# mcu.net
KiCad netlist of a schematic drawn in Altium Designer
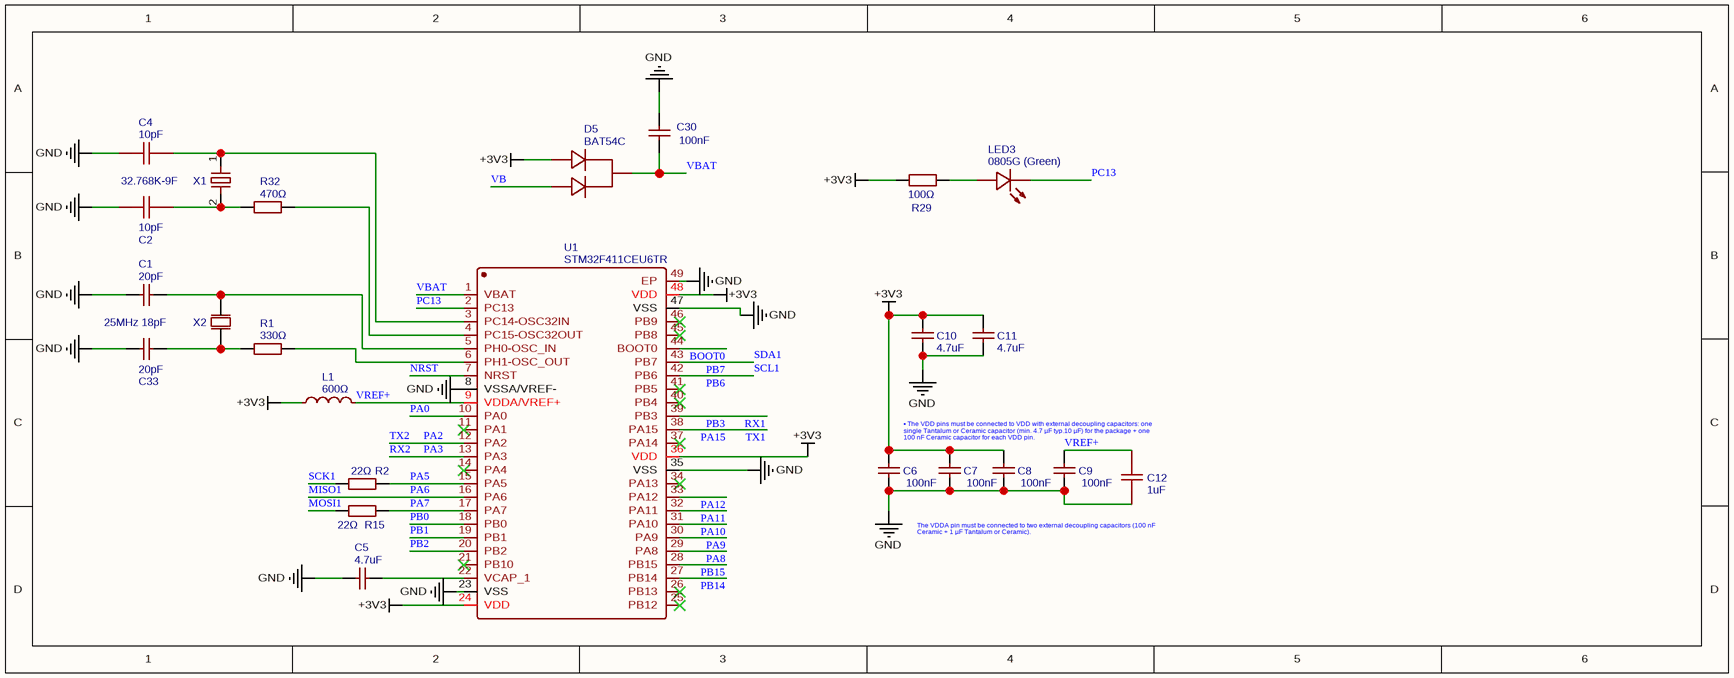
[diagram p0: mcu.schdoc]

(export (version "E")
  (design (tool "Eeschema 10.0.6"))
  (components
    (comp (ref "C1")
      (value "20pF")
      (fields (field (name "MANUFACTURER") "FH(风华)") (field (name "MANUFACTURER PART") "0402CG200J500NT"))
      (libsource (lib "") (part "root_0_20pF__1"))
    )
    (comp (ref "C2")
      (value "10pF")
      (fields
        (field (name "MANUFACTURER") "SAMSUNG(三星)")
        (field (name "MANUFACTURER PART") "CL05C100JB5NNNC")
      )
      (libsource (lib "") (part "root_0_10pF__1"))
    )
    (comp (ref "C4")
      (value "10pF")
      (fields
        (field (name "MANUFACTURER") "SAMSUNG(三星)")
        (field (name "MANUFACTURER PART") "CL05C100JB5NNNC")
      )
      (libsource (lib "altium-import") (part "root_0_10pF_"))
    )
    (comp (ref "C5")
      (value "4.7uF")
      (fields
        (field (name "MANUFACTURER PART") "CL05A475MP5NRNC")
        (field (name "MANUFACTURER") "SAMSUNG(三星)")
      )
      (libsource (lib "altium-import") (part "root_0_4.7uF_"))
    )
    (comp (ref "C6")
      (value "100nF")
      (fields
        (field (name "MANUFACTURER PART") "CL05B104KO5NNNC")
        (field (name "MANUFACTURER") "SAMSUNG(三星)")
      )
      (libsource (lib "altium-import") (part "root_3_100nF_"))
    )
    (comp (ref "C7")
      (value "100nF")
      (fields
        (field (name "MANUFACTURER PART") "CL05B104KO5NNNC")
        (field (name "MANUFACTURER") "SAMSUNG(三星)")
      )
      (libsource (lib "altium-import") (part "root_3_100nF_"))
    )
    (comp (ref "C8")
      (value "100nF")
      (fields
        (field (name "MANUFACTURER PART") "CL05B104KO5NNNC")
        (field (name "MANUFACTURER") "SAMSUNG(三星)")
      )
      (libsource (lib "altium-import") (part "root_3_100nF_"))
    )
    (comp (ref "C9")
      (value "100nF")
      (fields
        (field (name "MANUFACTURER PART") "CL05B104KO5NNNC")
        (field (name "MANUFACTURER") "SAMSUNG(三星)")
      )
      (libsource (lib "altium-import") (part "root_3_100nF_"))
    )
    (comp (ref "C10")
      (value "4.7uF")
      (fields
        (field (name "MANUFACTURER PART") "CL05A475MP5NRNC")
        (field (name "MANUFACTURER") "SAMSUNG(三星)")
      )
      (libsource (lib "altium-import") (part "root_3_4.7uF_"))
    )
    (comp (ref "C11")
      (value "4.7uF")
      (fields
        (field (name "MANUFACTURER PART") "CL05A475MP5NRNC")
        (field (name "MANUFACTURER") "SAMSUNG(三星)")
      )
      (libsource (lib "altium-import") (part "root_3_4.7uF_"))
    )
    (comp (ref "C12")
      (value "1uF")
      (fields
        (field (name "MANUFACTURER") "SAMSUNG(三星)")
        (field (name "MANUFACTURER PART") "CL05A105KA5NQNC")
      )
      (libsource (lib "altium-import") (part "root_3_1uF_"))
    )
    (comp (ref "C30")
      (value "100nF")
      (fields
        (field (name "MANUFACTURER PART") "CL05B104KO5NNNC")
        (field (name "MANUFACTURER") "SAMSUNG(三星)")
      )
      (libsource (lib "altium-import") (part "root_3_100nF_"))
    )
    (comp (ref "C33")
      (value "20pF")
      (fields (field (name "MANUFACTURER") "FH(风华)") (field (name "MANUFACTURER PART") "0402CG200J500NT"))
      (libsource (lib "altium-import") (part "root_0_20pF_"))
    )
    (comp (ref "D5")
      (value "BAT54C")
      (fields (field (name "MANUFACTURER") "CJ(江苏长电/长晶)"))
      (libsource (lib "altium-import") (part "root_0_BAT54C_"))
    )
    (comp (ref "L1")
      (value "600Ω")
      (fields (field (name "MANUFACTURER") "Sunlord(顺络)") (field (name "MANUFACTURER PART") "GZ1608D601TF"))
      (libsource (lib "altium-import") (part "root_0_600Ω_"))
    )
    (comp (ref "LED3")
      (value "0805G (Green)")
      (fields (field (name "MANUFACTURER") "KENTO") (field (name "MANUFACTURER PART") "KT-0805翠绿"))
      (libsource (lib "altium-import") (part "root_2_0805G (Green)_"))
    )
    (comp (ref "R1")
      (value "330Ω")
      (fields
        (field (name "MANUFACTURER") "UNI-ROYAL(厚声)")
        (field (name "MANUFACTURER PART") "0402WGF3300TCE")
      )
      (libsource (lib "altium-import") (part "root_0_330Ω_"))
    )
    (comp (ref "R2")
      (value "22Ω")
      (fields
        (field (name "MANUFACTURER") "UNI-ROYAL(厚声)")
        (field (name "MANUFACTURER PART") "0402WGF220JTCE")
      )
      (libsource (lib "altium-import") (part "root_0_22Ω_"))
    )
    (comp (ref "R15")
      (value "22Ω")
      (fields
        (field (name "MANUFACTURER") "UNI-ROYAL(厚声)")
        (field (name "MANUFACTURER PART") "0402WGF220JTCE")
      )
      (libsource (lib "altium-import") (part "root_0_22Ω_"))
    )
    (comp (ref "R29")
      (value "100Ω")
      (fields
        (field (name "MANUFACTURER") "UNI-ROYAL(厚声)")
        (field (name "MANUFACTURER PART") "0402WGF1000TCE")
      )
      (libsource (lib "altium-import") (part "root_0_100Ω_"))
    )
    (comp (ref "R32")
      (value "470Ω")
      (fields
        (field (name "MANUFACTURER") "UNI-ROYAL(厚声)")
        (field (name "MANUFACTURER PART") "0402WGF4700TCE")
      )
      (libsource (lib "altium-import") (part "root_0_470Ω_"))
    )
    (comp (ref "U1")
      (value "STM32F411CEU6TR")
      (fields (field (name "MANUFACTURER") "ST(意法半导体)") (field (name "CONTRIBUTOR") "LCSC"))
      (libsource (lib "altium-import") (part "root_0_STM32F411CEU6TR_"))
    )
    (comp (ref "X1")
      (value "32.768K-9F")
      (fields
        (field (name "MANUFACTURER PART") "CMTV-T1A-32.768K-12.5PF-20PPM")
        (field (name "CONTRIBUTOR") "lcsc")
      )
      (libsource (lib "altium-import") (part "root_3_32.768K-9F_"))
    )
    (comp (ref "X2")
      (value "25MHz 18pF")
      (fields
        (field (name "MANUFACTURER") "ABRACON")
        (field (name "MANUFACTURER PART") "ABM3-25.000MHZ-D2Y-T")
        (field (name "CONTRIBUTOR") "LCSC")
      )
      (libsource (lib "altium-import") (part "root_3_25MHz 18pF_"))
    )
  )
  (nets
    (net (code "1") (name "+3V3") (class "Default")
      (node (ref "C10") (pin "1") (pinfunction "1_1") (pintype "passive"))
      (node (ref "C11") (pin "1") (pinfunction "1_1") (pintype "passive"))
      (node (ref "C6") (pin "2") (pinfunction "2_2") (pintype "passive"))
      (node (ref "C7") (pin "2") (pinfunction "2_2") (pintype "passive"))
      (node (ref "C8") (pin "2") (pinfunction "2_2") (pintype "passive"))
      (node (ref "D5") (pin "1") (pinfunction "A1_1") (pintype "passive"))
      (node (ref "L1") (pin "1") (pinfunction "1_1") (pintype "passive"))
      (node (ref "R29") (pin "1") (pinfunction "1_1") (pintype "passive"))
      (node (ref "U1") (pin "24") (pinfunction "VDD_24") (pintype "passive"))
      (node (ref "U1") (pin "36") (pinfunction "VDD_36") (pintype "passive"))
      (node (ref "U1") (pin "48") (pinfunction "VDD_48") (pintype "passive"))
    )
    (net (code "2") (name "/BOOT0") (class "Default")
      (node (ref "U1") (pin "44") (pinfunction "BOOT0_44") (pintype "passive"))
    )
    (net (code "3") (name "/MISO1") (class "Default")
      (node (ref "U1") (pin "16") (pinfunction "PA6_16") (pintype "passive"))
    )
    (net (code "4") (name "/MOSI1") (class "Default")
      (node (ref "R15") (pin "1") (pinfunction "1_1") (pintype "passive"))
    )
    (net (code "5") (name "/NRST") (class "Default")
      (node (ref "U1") (pin "7") (pinfunction "NRST_7") (pintype "passive"))
    )
    (net (code "6") (name "/PA0") (class "Default")
      (node (ref "U1") (pin "10") (pinfunction "PA0_10") (pintype "passive"))
    )
    (net (code "7") (name "/PA2") (class "Default")
      (node (ref "U1") (pin "12") (pinfunction "PA2_12") (pintype "passive"))
    )
    (net (code "8") (name "/PA3") (class "Default")
      (node (ref "U1") (pin "13") (pinfunction "PA3_13") (pintype "passive"))
    )
    (net (code "9") (name "/PA5") (class "Default")
      (node (ref "R2") (pin "2") (pinfunction "2_2") (pintype "passive"))
      (node (ref "U1") (pin "15") (pinfunction "PA5_15") (pintype "passive"))
    )
    (net (code "10") (name "/PA7") (class "Default")
      (node (ref "R15") (pin "2") (pinfunction "2_2") (pintype "passive"))
      (node (ref "U1") (pin "17") (pinfunction "PA7_17") (pintype "passive"))
    )
    (net (code "11") (name "/PA8") (class "Default")
      (node (ref "U1") (pin "29") (pinfunction "PA8_29") (pintype "passive"))
    )
    (net (code "12") (name "/PA9") (class "Default")
      (node (ref "U1") (pin "30") (pinfunction "PA9_30") (pintype "passive"))
    )
    (net (code "13") (name "/PA10") (class "Default")
      (node (ref "U1") (pin "31") (pinfunction "PA10_31") (pintype "passive"))
    )
    (net (code "14") (name "/PA11") (class "Default")
      (node (ref "U1") (pin "32") (pinfunction "PA11_32") (pintype "passive"))
    )
    (net (code "15") (name "/PA12") (class "Default")
      (node (ref "U1") (pin "33") (pinfunction "PA12_33") (pintype "passive"))
    )
    (net (code "16") (name "/PA15") (class "Default")
      (node (ref "U1") (pin "38") (pinfunction "PA15_38") (pintype "passive"))
    )
    (net (code "17") (name "/PB0") (class "Default")
      (node (ref "U1") (pin "18") (pinfunction "PB0_18") (pintype "passive"))
    )
    (net (code "18") (name "/PB1") (class "Default")
      (node (ref "U1") (pin "19") (pinfunction "PB1_19") (pintype "passive"))
    )
    (net (code "19") (name "/PB2") (class "Default")
      (node (ref "U1") (pin "20") (pinfunction "PB2_20") (pintype "passive"))
    )
    (net (code "20") (name "/PB3") (class "Default")
      (node (ref "U1") (pin "39") (pinfunction "PB3_39") (pintype "passive"))
    )
    (net (code "21") (name "/PB6") (class "Default")
      (node (ref "U1") (pin "42") (pinfunction "PB6_42") (pintype "passive"))
    )
    (net (code "22") (name "/PB7") (class "Default")
      (node (ref "U1") (pin "43") (pinfunction "PB7_43") (pintype "passive"))
    )
    (net (code "23") (name "/PB14") (class "Default")
      (node (ref "U1") (pin "27") (pinfunction "PB14_27") (pintype "passive"))
    )
    (net (code "24") (name "/PB15") (class "Default")
      (node (ref "U1") (pin "28") (pinfunction "PB15_28") (pintype "passive"))
    )
    (net (code "25") (name "/PC13") (class "Default")
      (node (ref "LED3") (pin "2") (pinfunction "K_2") (pintype "passive"))
      (node (ref "U1") (pin "2") (pinfunction "PC13_2") (pintype "passive"))
    )
    (net (code "26") (name "/SCK1") (class "Default")
      (node (ref "R2") (pin "1") (pinfunction "1_1") (pintype "passive"))
    )
    (net (code "27") (name "/VB") (class "Default")
      (node (ref "D5") (pin "2") (pinfunction "A2_2") (pintype "passive"))
    )
    (net (code "28") (name "/VBAT") (class "Default")
      (node (ref "C30") (pin "1") (pinfunction "1_1") (pintype "passive"))
      (node (ref "D5") (pin "3") (pinfunction "K_3") (pintype "passive"))
      (node (ref "U1") (pin "1") (pinfunction "VBAT_1") (pintype "passive"))
    )
    (net (code "29") (name "/VREF+") (class "Default")
      (node (ref "C12") (pin "2") (pinfunction "2_2") (pintype "passive"))
      (node (ref "C9") (pin "2") (pinfunction "2_2") (pintype "passive"))
      (node (ref "L1") (pin "2") (pinfunction "2_2") (pintype "passive"))
      (node (ref "U1") (pin "9") (pinfunction "VDDA/VREF+_9") (pintype "passive"))
    )
    (net (code "30") (name "GND") (class "Default")
      (node (ref "C1") (pin "1") (pinfunction "1_1") (pintype "passive"))
      (node (ref "C10") (pin "2") (pinfunction "2_2") (pintype "passive"))
      (node (ref "C11") (pin "2") (pinfunction "2_2") (pintype "passive"))
      (node (ref "C12") (pin "1") (pinfunction "1_1") (pintype "passive"))
      (node (ref "C2") (pin "1") (pinfunction "1_1") (pintype "passive"))
      (node (ref "C30") (pin "2") (pinfunction "2_2") (pintype "passive"))
      (node (ref "C33") (pin "1") (pinfunction "1_1") (pintype "passive"))
      (node (ref "C4") (pin "1") (pinfunction "1_1") (pintype "passive"))
      (node (ref "C5") (pin "1") (pinfunction "1_1") (pintype "passive"))
      (node (ref "C6") (pin "1") (pinfunction "1_1") (pintype "passive"))
      (node (ref "C7") (pin "1") (pinfunction "1_1") (pintype "passive"))
      (node (ref "C8") (pin "1") (pinfunction "1_1") (pintype "passive"))
      (node (ref "C9") (pin "1") (pinfunction "1_1") (pintype "passive"))
      (node (ref "U1") (pin "23") (pinfunction "VSS_23") (pintype "passive"))
      (node (ref "U1") (pin "35") (pinfunction "VSS_35") (pintype "passive"))
      (node (ref "U1") (pin "47") (pinfunction "VSS_47") (pintype "passive"))
      (node (ref "U1") (pin "49") (pinfunction "EP_49") (pintype "passive"))
      (node (ref "U1") (pin "8") (pinfunction "VSSA/VREF-_8") (pintype "passive"))
    )
    (net (code "31") (name "Net-(C2-Pad2)") (class "Default")
      (node (ref "C2") (pin "2") (pinfunction "2_2") (pintype "passive"))
      (node (ref "R32") (pin "1") (pinfunction "1_1") (pintype "passive"))
      (node (ref "X1") (pin "2") (pinfunction "2_2") (pintype "passive"))
    )
    (net (code "32") (name "Net-(LED3-A)") (class "Default")
      (node (ref "LED3") (pin "1") (pinfunction "A_1") (pintype "passive"))
      (node (ref "R29") (pin "2") (pinfunction "2_2") (pintype "passive"))
    )
    (net (code "33") (name "Net-(U1-PC14-OSC32IN)") (class "Default")
      (node (ref "C4") (pin "2") (pinfunction "2_2") (pintype "passive"))
      (node (ref "U1") (pin "3") (pinfunction "PC14-OSC32IN_3") (pintype "passive"))
      (node (ref "X1") (pin "1") (pinfunction "1_1") (pintype "passive"))
    )
    (net (code "34") (name "Net-(U1-PC15-OSC32OUT)") (class "Default")
      (node (ref "R32") (pin "2") (pinfunction "2_2") (pintype "passive"))
      (node (ref "U1") (pin "4") (pinfunction "PC15-OSC32OUT_4") (pintype "passive"))
    )
    (net (code "35") (name "Net-(U1-PH0-OSC_IN)") (class "Default")
      (node (ref "C1") (pin "2") (pinfunction "2_2") (pintype "passive"))
      (node (ref "U1") (pin "5") (pinfunction "PH0-OSC_IN_5") (pintype "passive"))
      (node (ref "X2") (pin "1") (pinfunction "OSC1_1") (pintype "passive"))
    )
    (net (code "36") (name "Net-(U1-PH1-OSC_OUT)") (class "Default")
      (node (ref "R1") (pin "2") (pinfunction "2_2") (pintype "passive"))
      (node (ref "U1") (pin "6") (pinfunction "PH1-OSC_OUT_6") (pintype "passive"))
    )
    (net (code "37") (name "Net-(U1-VCAP_1)") (class "Default")
      (node (ref "C5") (pin "2") (pinfunction "2_2") (pintype "passive"))
      (node (ref "U1") (pin "22") (pinfunction "VCAP_1_22") (pintype "passive"))
    )
    (net (code "38") (name "Net-(X2-OSC2)") (class "Default")
      (node (ref "C33") (pin "2") (pinfunction "2_2") (pintype "passive"))
      (node (ref "R1") (pin "1") (pinfunction "1_1") (pintype "passive"))
      (node (ref "X2") (pin "2") (pinfunction "OSC2_2") (pintype "passive"))
    )
    (net (code "39") (name "unconnected-(U1-PA1-Pad11)") (class "Default")
      (node (ref "U1") (pin "11") (pinfunction "PA1_11") (pintype "passive+no_connect"))
    )
    (net (code "40") (name "unconnected-(U1-PA4-Pad14)") (class "Default")
      (node (ref "U1") (pin "14") (pinfunction "PA4_14") (pintype "passive+no_connect"))
    )
    (net (code "41") (name "unconnected-(U1-PA13-Pad34)") (class "Default")
      (node (ref "U1") (pin "34") (pinfunction "PA13_34") (pintype "passive+no_connect"))
    )
    (net (code "42") (name "unconnected-(U1-PA14-Pad37)") (class "Default")
      (node (ref "U1") (pin "37") (pinfunction "PA14_37") (pintype "passive+no_connect"))
    )
    (net (code "43") (name "unconnected-(U1-PB4-Pad40)") (class "Default")
      (node (ref "U1") (pin "40") (pinfunction "PB4_40") (pintype "passive+no_connect"))
    )
    (net (code "44") (name "unconnected-(U1-PB5-Pad41)") (class "Default")
      (node (ref "U1") (pin "41") (pinfunction "PB5_41") (pintype "passive+no_connect"))
    )
    (net (code "45") (name "unconnected-(U1-PB8-Pad45)") (class "Default")
      (node (ref "U1") (pin "45") (pinfunction "PB8_45") (pintype "passive+no_connect"))
    )
    (net (code "46") (name "unconnected-(U1-PB9-Pad46)") (class "Default")
      (node (ref "U1") (pin "46") (pinfunction "PB9_46") (pintype "passive+no_connect"))
    )
    (net (code "47") (name "unconnected-(U1-PB10-Pad21)") (class "Default")
      (node (ref "U1") (pin "21") (pinfunction "PB10_21") (pintype "passive+no_connect"))
    )
    (net (code "48") (name "unconnected-(U1-PB12-Pad25)") (class "Default")
      (node (ref "U1") (pin "25") (pinfunction "PB12_25") (pintype "passive+no_connect"))
    )
    (net (code "49") (name "unconnected-(U1-PB13-Pad26)") (class "Default")
      (node (ref "U1") (pin "26") (pinfunction "PB13_26") (pintype "passive+no_connect"))
    )
  )
)
